# utilidong-lipo-charger_soc-mk-1_0.net
KiCad netlist of a schematic drawn in EAGLE
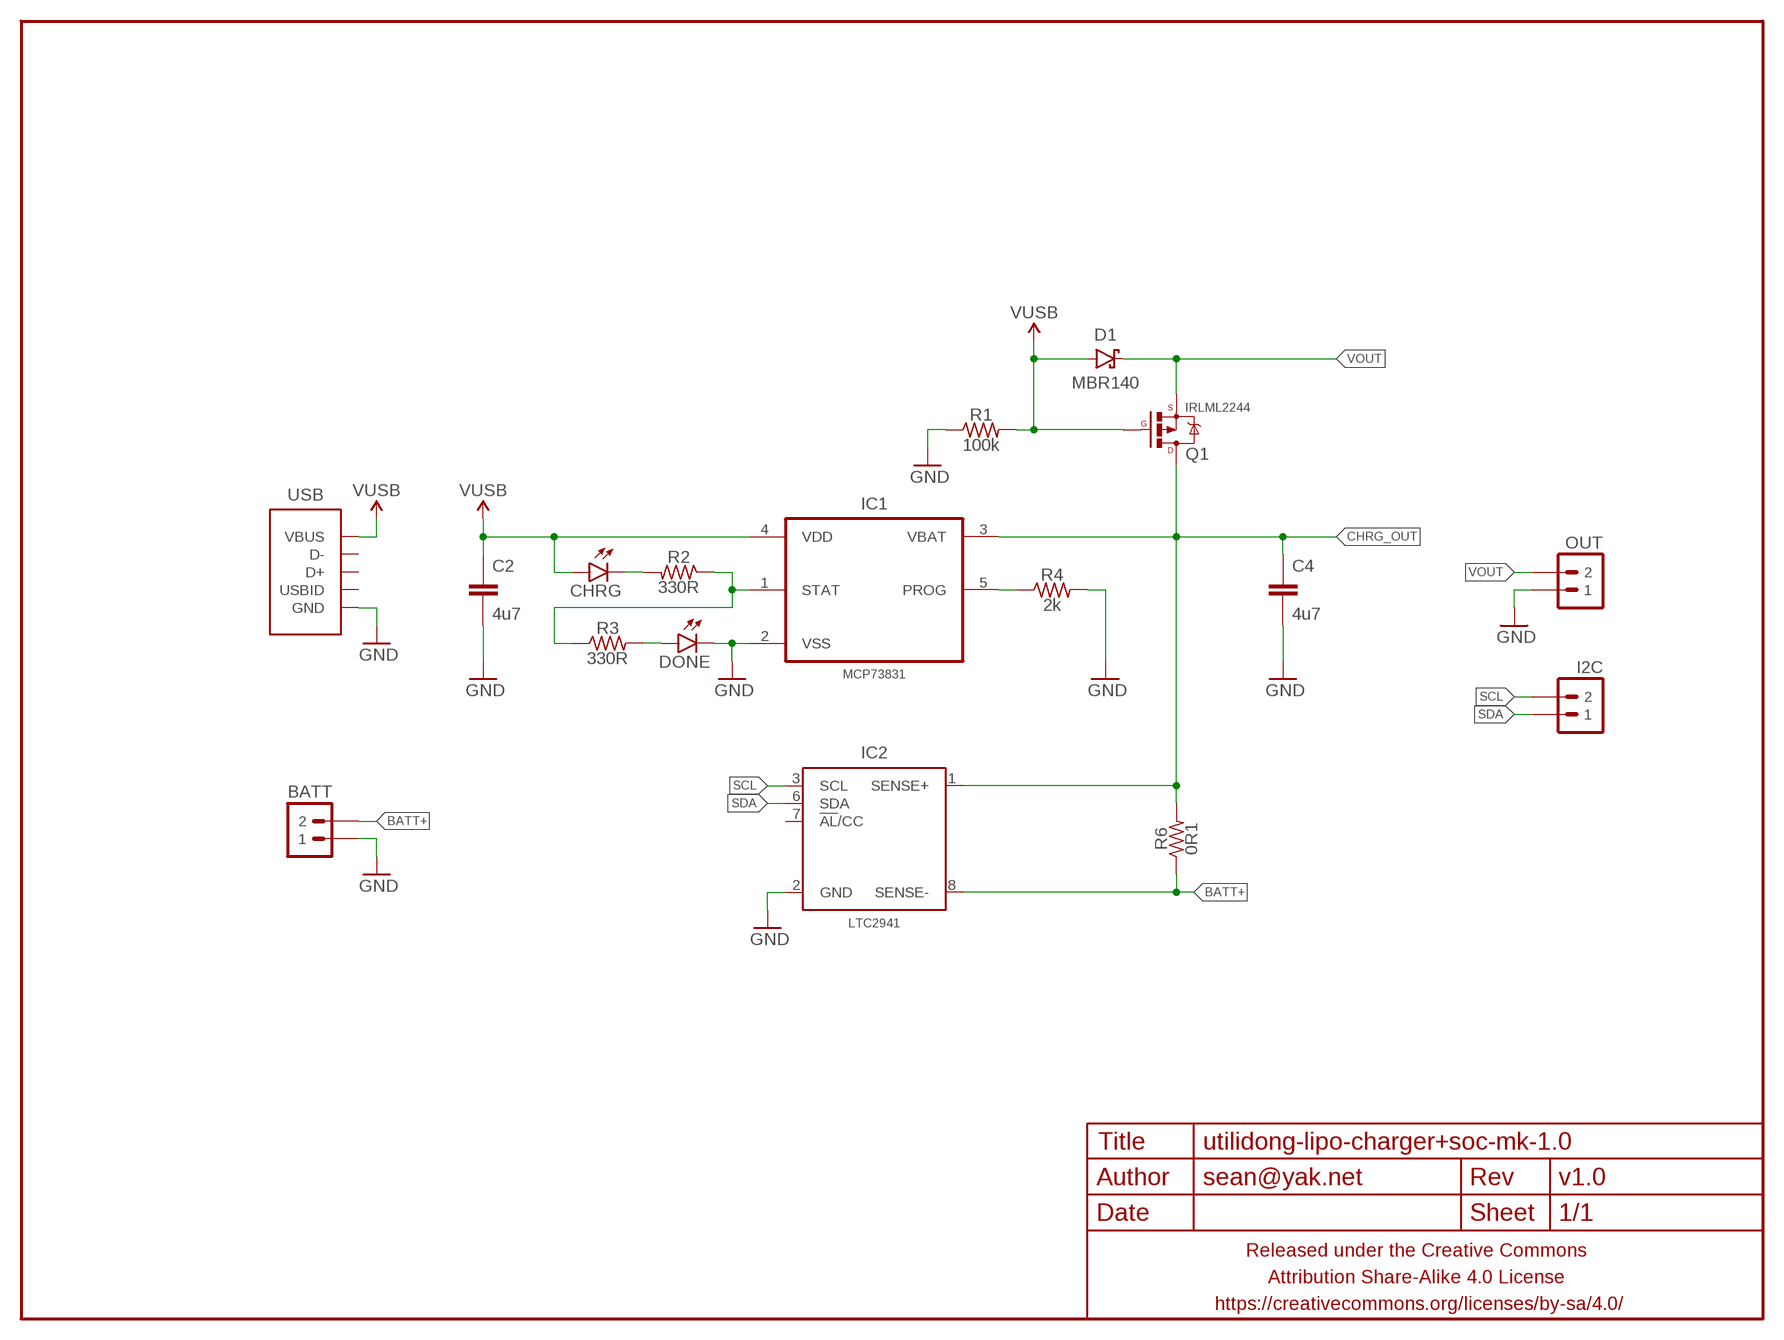
[diagram p0: schematic, sheet 1]

(export (version "E")
  (design (tool "Eeschema 10.0.6"))
  (components
    (comp (ref "BATT")
      (value "M02PTH-CENTERED-R+")
      (footprint "eagle-import:1X02-CENTER-R+")
      (libsource (lib "eagle-import") (part "M02PTH-CENTERED-R+"))
    )
    (comp (ref "C2")
      (value "4u7")
      (footprint "eagle-import:C0603")
      (libsource (lib "eagle-import") (part "CAPACITOR-CERAMICC0603"))
    )
    (comp (ref "C4")
      (value "4u7")
      (footprint "eagle-import:C0603")
      (libsource (lib "eagle-import") (part "CAPACITOR-CERAMICC0603"))
    )
    (comp (ref "CHRG")
      (value "LED0603")
      (footprint "eagle-import:LED-0603")
      (libsource (lib "eagle-import") (part "LED0603"))
    )
    (comp (ref "D1")
      (value "MBR140")
      (footprint "eagle-import:SOD123-SCHOTTKY")
      (libsource (lib "eagle-import") (part "DIODE-SCHOTTKYSOD123"))
    )
    (comp (ref "DONE")
      (value "LED0603")
      (footprint "eagle-import:LED-0603")
      (libsource (lib "eagle-import") (part "LED0603"))
    )
    (comp (ref "FRAME1")
      (value "FRAME-LETTERNO_PACKAGE")
      (footprint "eagle-import:DUMMY")
      (fields (field (name "DESIGNER") "sean@yak.net") (field (name "VERSION") "v1.0"))
      (libsource (lib "eagle-import") (part "FRAME-LETTERNO_PACKAGE"))
    )
    (comp (ref "I2C")
      (value "M02PTH")
      (footprint "eagle-import:1X02")
      (libsource (lib "eagle-import") (part "M02PTH"))
    )
    (comp (ref "IC1")
      (value "MCP73831")
      (footprint "eagle-import:SOT95P280X145-5N")
      (fields (field (name "MPN") "MCP73831T-2ACI/OT"))
      (libsource (lib "eagle-import") (part "MCP73831T-2ACI/OT"))
    )
    (comp (ref "IC2")
      (value "LTC2941")
      (footprint "eagle-import:MSOP-8")
      (libsource (lib "eagle-import") (part "LTC2941MSOP-8"))
    )
    (comp (ref "OUT")
      (value "M02PTH-CENTERED-R+")
      (footprint "eagle-import:1X02-CENTER-R+")
      (libsource (lib "eagle-import") (part "M02PTH-CENTERED-R+"))
    )
    (comp (ref "Q1")
      (value "IRLML2244")
      (footprint "eagle-import:SOT23-3")
      (libsource (lib "eagle-import") (part "MOSFET-PCHANNELIRLML2244"))
    )
    (comp (ref "R1")
      (value "100k")
      (footprint "eagle-import:R0603")
      (libsource (lib "eagle-import") (part "RESISTORR0603"))
    )
    (comp (ref "R2")
      (value "330R")
      (footprint "eagle-import:R0603")
      (libsource (lib "eagle-import") (part "RESISTORR0603"))
    )
    (comp (ref "R3")
      (value "330R")
      (footprint "eagle-import:R0603")
      (libsource (lib "eagle-import") (part "RESISTORR0603"))
    )
    (comp (ref "R4")
      (value "2k")
      (footprint "eagle-import:R0603")
      (libsource (lib "eagle-import") (part "RESISTORR0603"))
    )
    (comp (ref "R6")
      (value "0R1")
      (footprint "eagle-import:R0603")
      (libsource (lib "eagle-import") (part "RESISTORR0603"))
    )
    (comp (ref "USB")
      (value "USB-ABFCI-10103594-USB-MICRO-B-LESS")
      (footprint "eagle-import:FCI-10103594-USB-MICRO-B-LESS")
      (libsource (lib "eagle-import") (part "USB-ABFCI-10103594-USB-MICRO-B-LESS"))
    )
  )
  (nets
    (net (code "1") (name "BATT+") (class "Default")
      (node (ref "BATT") (pin "2") (pinfunction "2_2") (pintype "passive"))
      (node (ref "IC2") (pin "8") (pinfunction "SENSE-_8") (pintype "bidirectional"))
      (node (ref "R6") (pin "1") (pinfunction "1_1") (pintype "passive"))
    )
    (net (code "2") (name "CHRG_OUT") (class "Default")
      (node (ref "C4") (pin "1") (pinfunction "1_1") (pintype "passive"))
      (node (ref "IC1") (pin "3") (pinfunction "VBAT_3") (pintype "output"))
      (node (ref "IC2") (pin "1") (pinfunction "SENSE+_1") (pintype "bidirectional"))
      (node (ref "Q1") (pin "3") (pinfunction "D_3") (pintype "passive"))
      (node (ref "R6") (pin "2") (pinfunction "2_2") (pintype "passive"))
    )
    (net (code "3") (name "GND") (class "Default")
      (node (ref "BATT") (pin "1") (pinfunction "1_1") (pintype "passive"))
      (node (ref "C2") (pin "2") (pinfunction "2_2") (pintype "passive"))
      (node (ref "C4") (pin "2") (pinfunction "2_2") (pintype "passive"))
      (node (ref "DONE") (pin "C") (pinfunction "C_C") (pintype "passive"))
      (node (ref "IC1") (pin "2") (pinfunction "VSS_2") (pintype "power_in"))
      (node (ref "IC2") (pin "2") (pinfunction "GND_2") (pintype "bidirectional"))
      (node (ref "OUT") (pin "1") (pinfunction "1_1") (pintype "passive"))
      (node (ref "R1") (pin "1") (pinfunction "1_1") (pintype "passive"))
      (node (ref "R4") (pin "2") (pinfunction "2_2") (pintype "passive"))
      (node (ref "USB") (pin "5") (pinfunction "GND_5") (pintype "bidirectional"))
    )
    (net (code "4") (name "Net-(CHRG-PadC)") (class "Default")
      (node (ref "CHRG") (pin "C") (pinfunction "C_C") (pintype "passive"))
      (node (ref "R2") (pin "2") (pinfunction "2_2") (pintype "passive"))
    )
    (net (code "5") (name "Net-(DONE-PadA)") (class "Default")
      (node (ref "DONE") (pin "A") (pinfunction "A_A") (pintype "passive"))
      (node (ref "R3") (pin "2") (pinfunction "2_2") (pintype "passive"))
    )
    (net (code "6") (name "Net-(IC1-PROG)") (class "Default")
      (node (ref "IC1") (pin "5") (pinfunction "PROG_5") (pintype "input"))
      (node (ref "R4") (pin "1") (pinfunction "1_1") (pintype "passive"))
    )
    (net (code "7") (name "Net-(IC1-STAT)") (class "Default")
      (node (ref "IC1") (pin "1") (pinfunction "STAT_1") (pintype "output"))
      (node (ref "R2") (pin "1") (pinfunction "1_1") (pintype "passive"))
      (node (ref "R3") (pin "1") (pinfunction "1_1") (pintype "passive"))
    )
    (net (code "8") (name "SCL") (class "Default")
      (node (ref "I2C") (pin "2") (pinfunction "2_2") (pintype "passive"))
      (node (ref "IC2") (pin "3") (pinfunction "SCL_3") (pintype "bidirectional"))
    )
    (net (code "9") (name "SDA") (class "Default")
      (node (ref "I2C") (pin "1") (pinfunction "1_1") (pintype "passive"))
      (node (ref "IC2") (pin "6") (pinfunction "SDA_6") (pintype "bidirectional"))
    )
    (net (code "10") (name "VOUT") (class "Default")
      (node (ref "D1") (pin "C") (pinfunction "C_C") (pintype "passive"))
      (node (ref "OUT") (pin "2") (pinfunction "2_2") (pintype "passive"))
      (node (ref "Q1") (pin "2") (pinfunction "S_2") (pintype "passive"))
    )
    (net (code "11") (name "VUSB") (class "Default")
      (node (ref "C2") (pin "1") (pinfunction "1_1") (pintype "passive"))
      (node (ref "CHRG") (pin "A") (pinfunction "A_A") (pintype "passive"))
      (node (ref "D1") (pin "A") (pinfunction "A_A") (pintype "passive"))
      (node (ref "IC1") (pin "4") (pinfunction "VDD_4") (pintype "power_in"))
      (node (ref "Q1") (pin "1") (pinfunction "G_1") (pintype "passive"))
      (node (ref "R1") (pin "2") (pinfunction "2_2") (pintype "passive"))
      (node (ref "USB") (pin "1") (pinfunction "VBUS_1") (pintype "bidirectional"))
    )
    (net (code "12") (name "unconnected-(IC2-~{AL}{slash}CC-Pad7)") (class "Default")
      (node (ref "IC2") (pin "7") (pinfunction "~{AL}/CC_7") (pintype "bidirectional"))
    )
    (net (code "13") (name "unconnected-(USB-D+-Pad3)") (class "Default")
      (node (ref "USB") (pin "3") (pinfunction "D+_3") (pintype "bidirectional"))
    )
    (net (code "14") (name "unconnected-(USB-D--Pad2)") (class "Default")
      (node (ref "USB") (pin "2") (pinfunction "D-_2") (pintype "bidirectional"))
    )
    (net (code "15") (name "unconnected-(USB-USBID-Pad4)") (class "Default")
      (node (ref "USB") (pin "4") (pinfunction "USBID_4") (pintype "bidirectional"))
    )
  )
)
